# 2_Microcontroler_48.net
KiCad netlist of a schematic drawn in Altium Designer
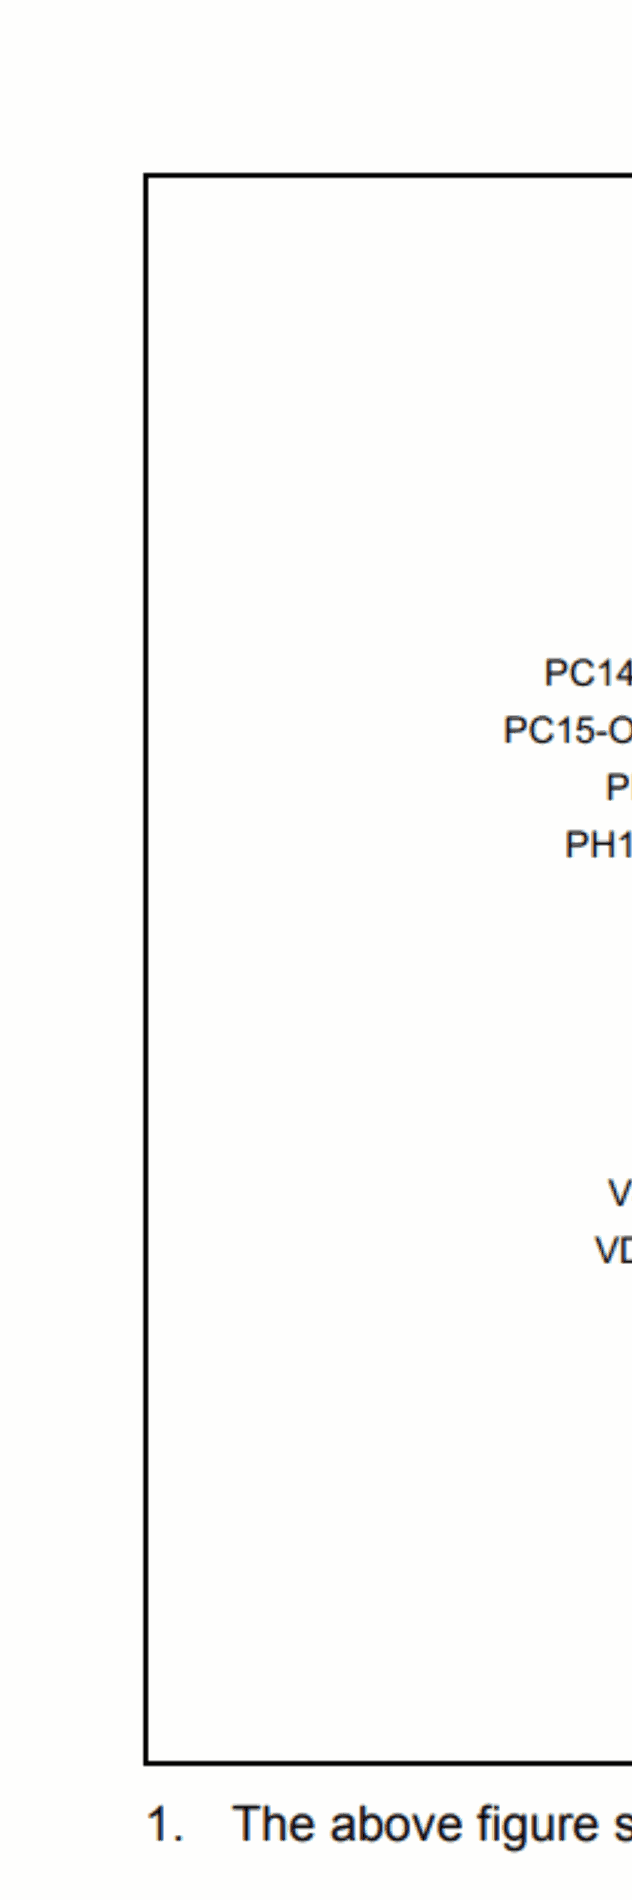
[diagram p0: 2_Microcontroler_48.SchDoc, top left]
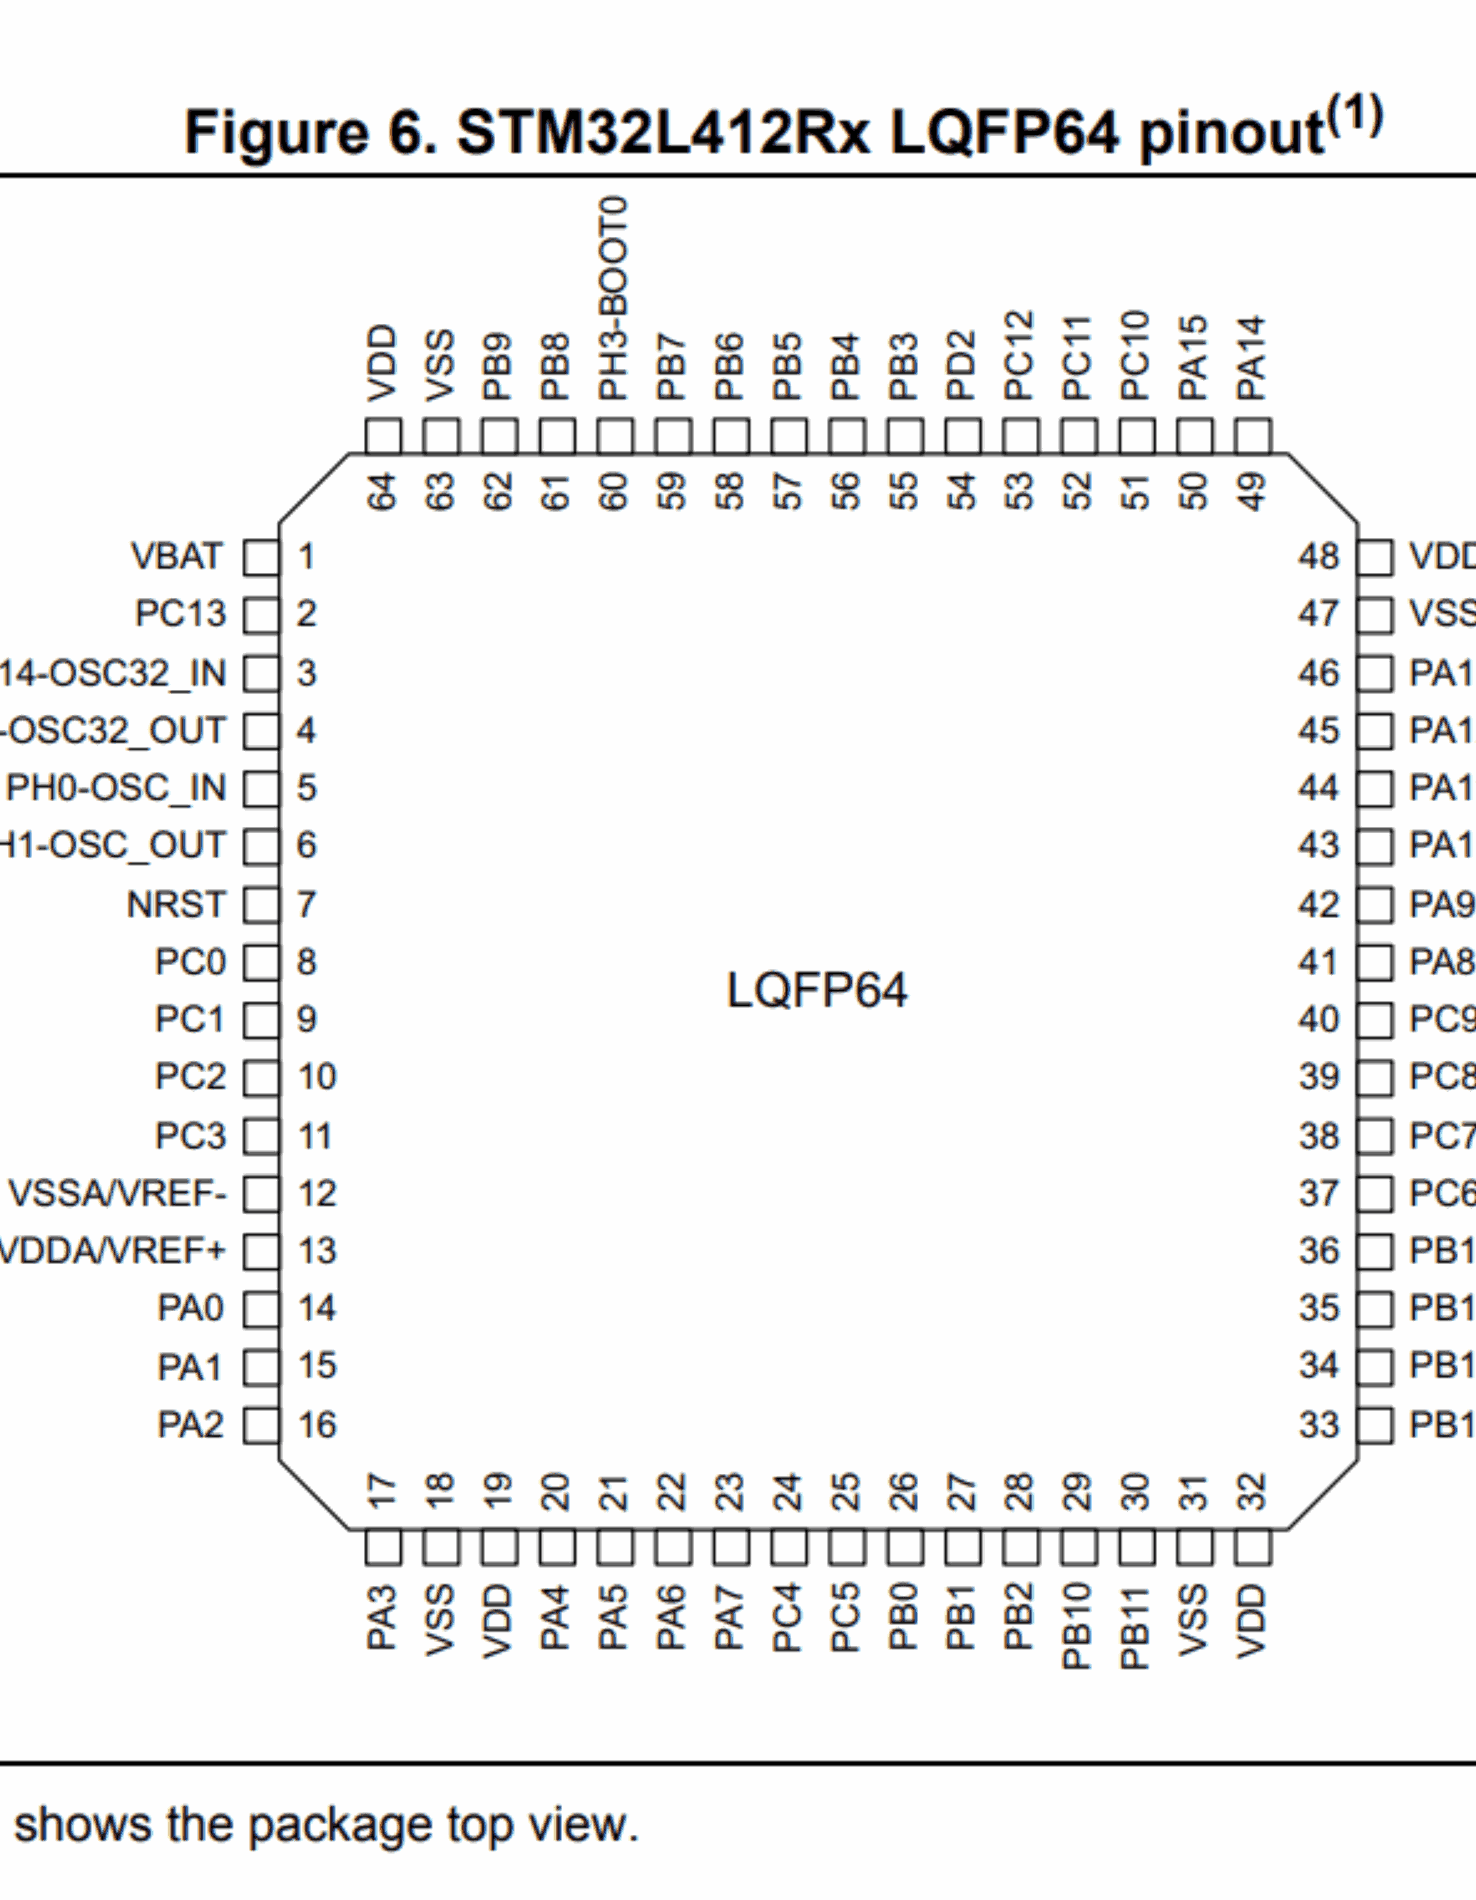
[diagram p1: 2_Microcontroler_48.SchDoc, top middle]
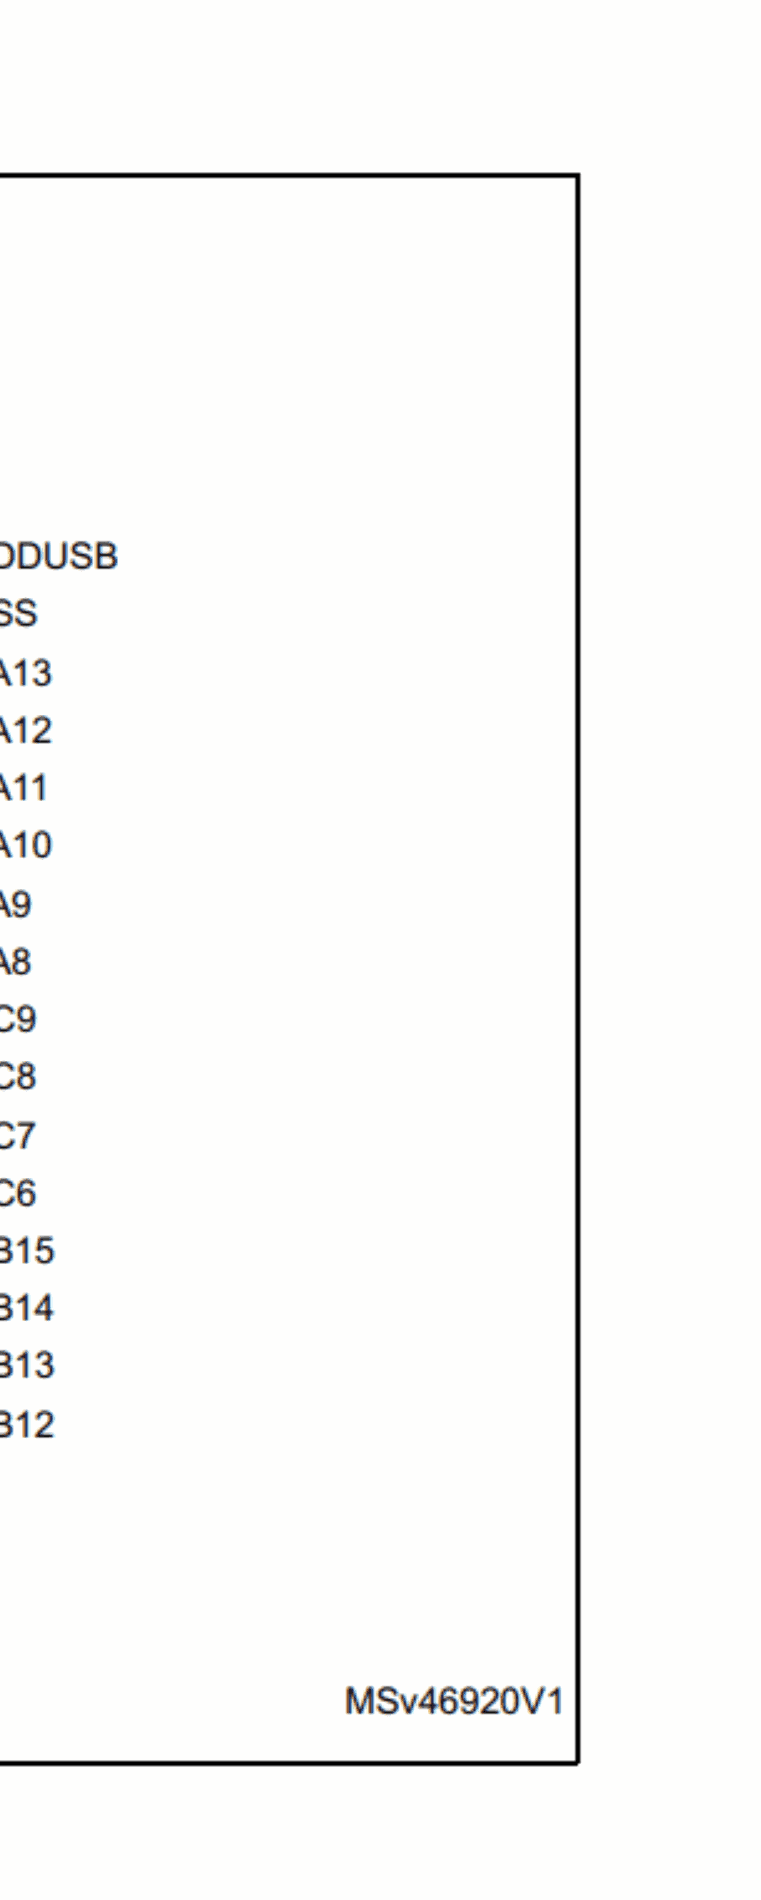
[diagram p2: 2_Microcontroler_48.SchDoc, top right]
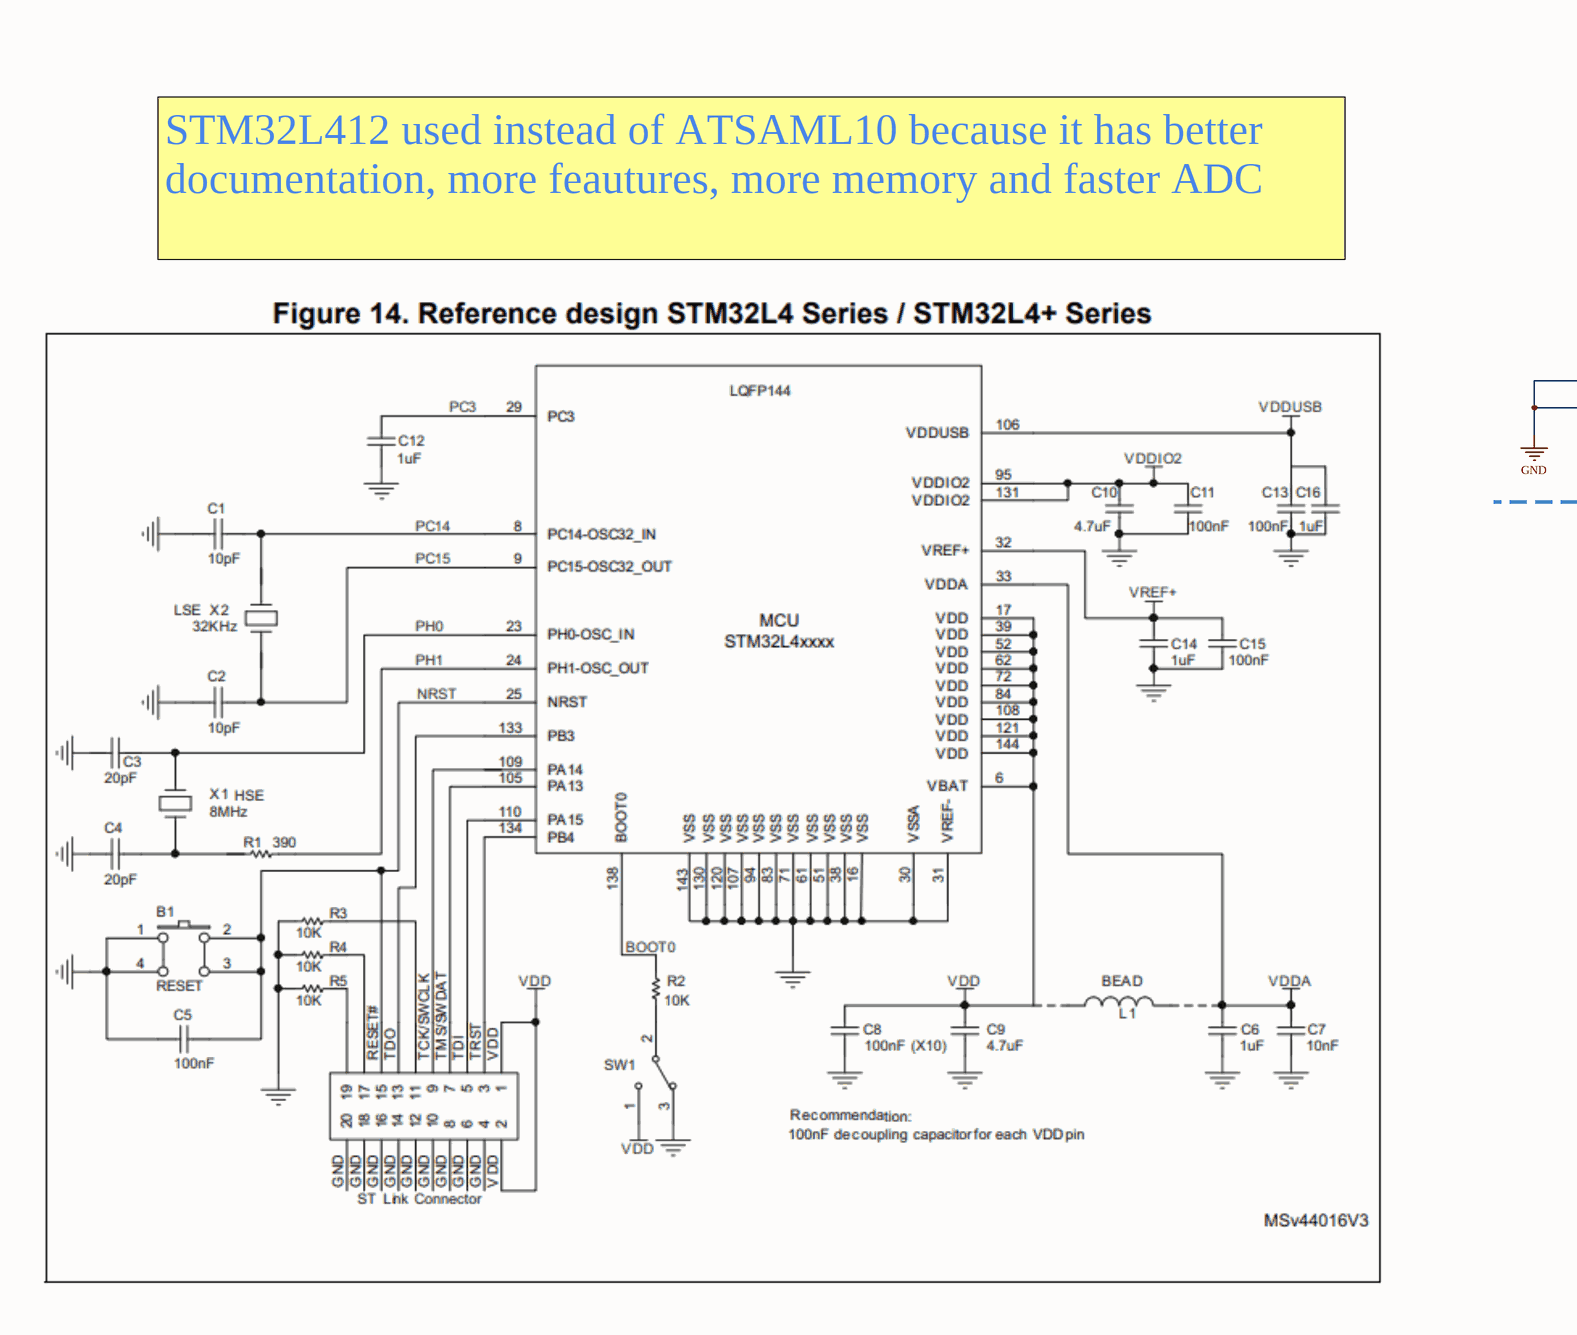
[diagram p3: 2_Microcontroler_48.SchDoc, bottom left]
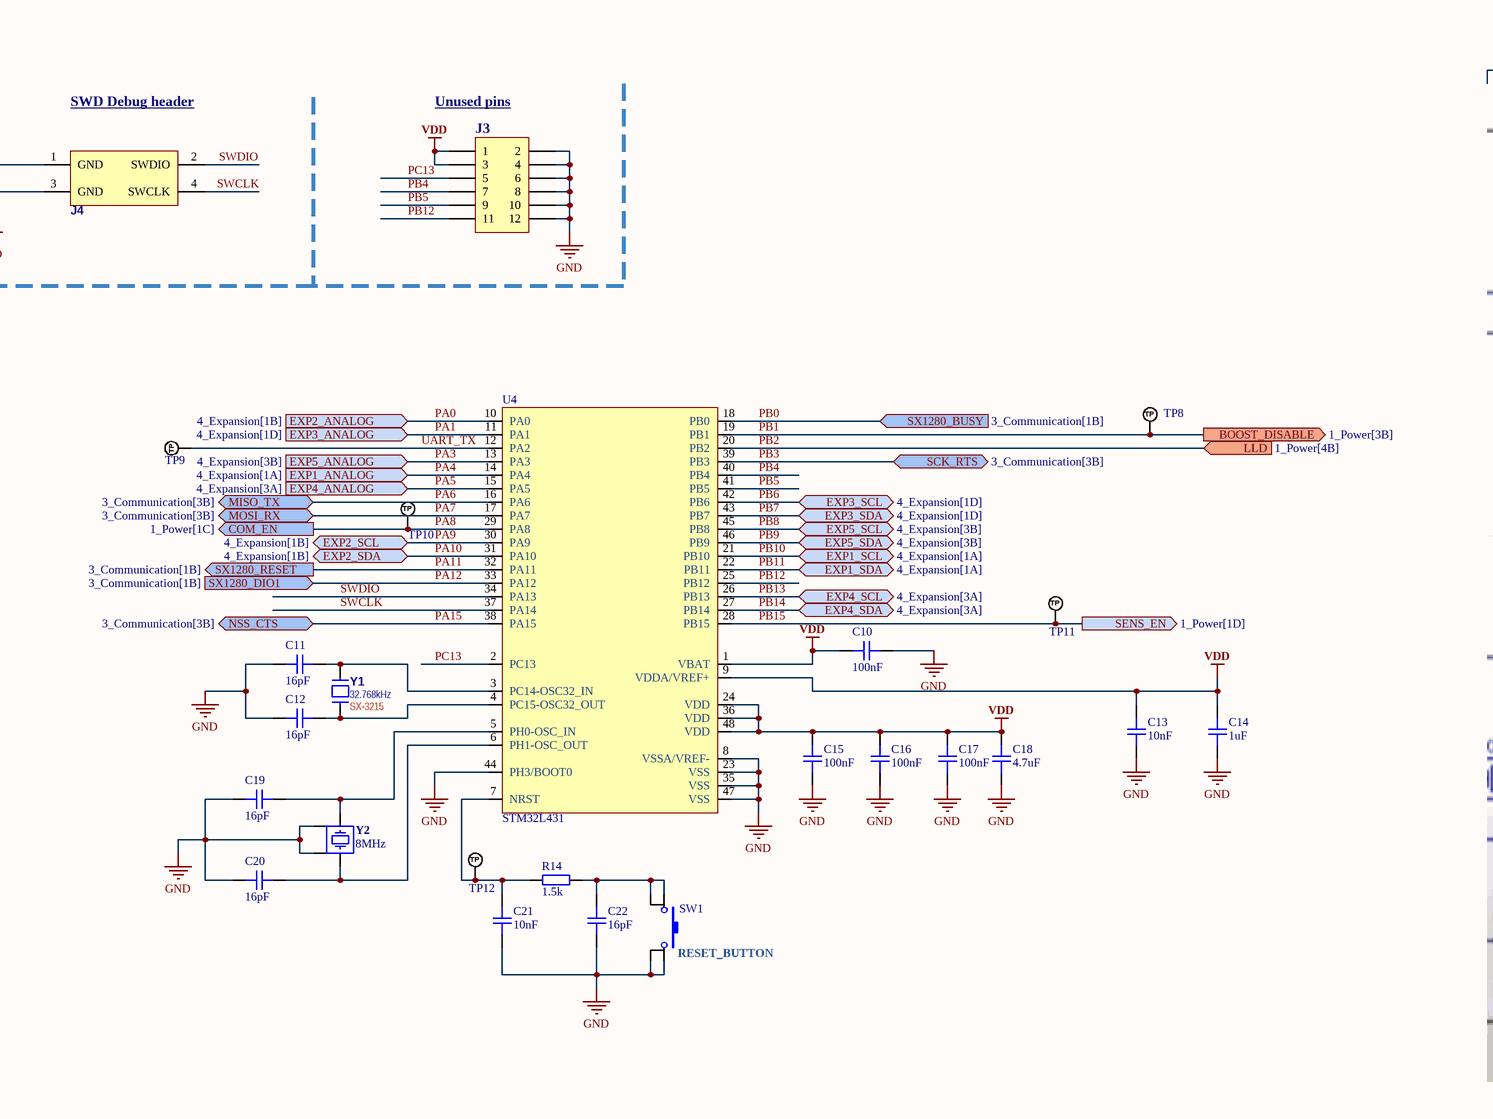
[diagram p4: 2_Microcontroler_48.SchDoc, bottom middle]
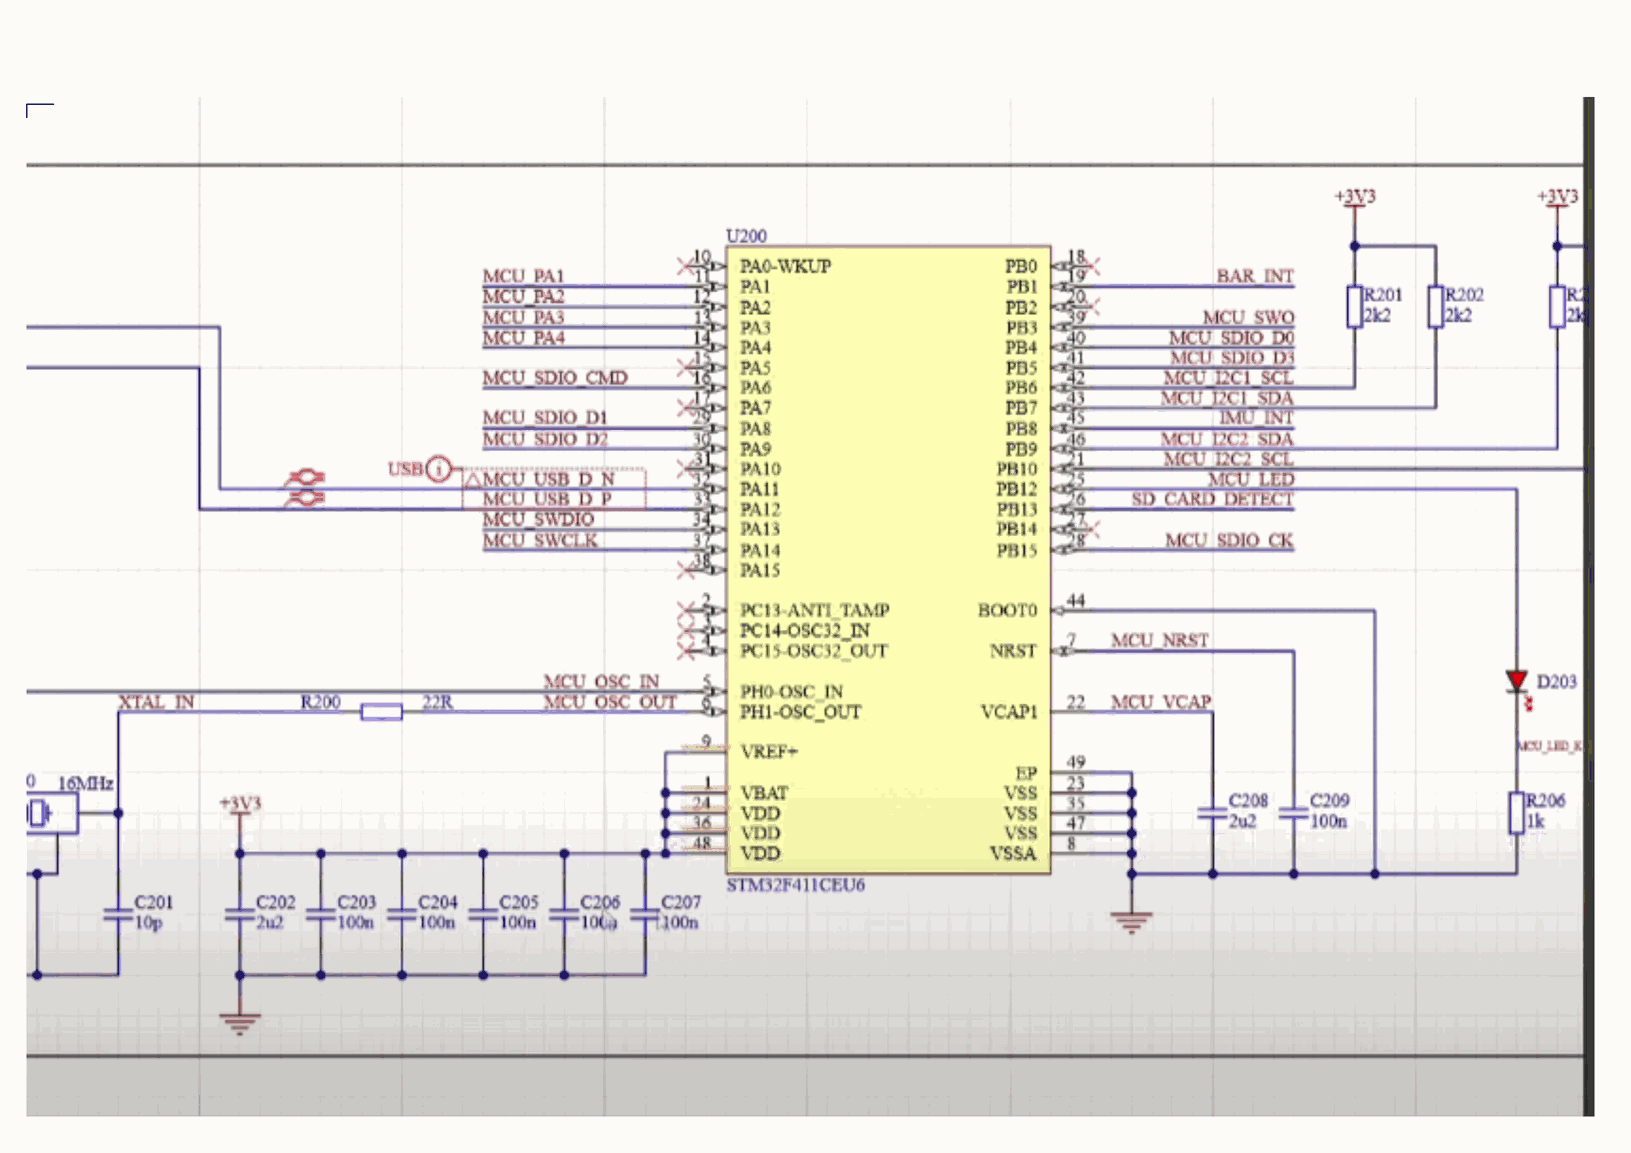
[diagram p5: 2_Microcontroler_48.SchDoc, bottom right]

(export (version "E")
  (design (tool "Eeschema 10.0.6"))
  (components
    (comp (ref "C10")
      (value "100nF")
      (footprint "C0603")
      (description "Capacitor SMD 0603")
      (libsource (lib "Schlib_H2") (part "CAP_0603"))
    )
    (comp (ref "C11")
      (value "16pF")
      (footprint "C0603")
      (description "Capacitor SMD 0603")
      (libsource (lib "Schlib_H2") (part "CAP_0603"))
    )
    (comp (ref "C12")
      (value "16pF")
      (footprint "C0603")
      (description "Capacitor SMD 0603")
      (libsource (lib "Schlib_H2") (part "CAP_0603"))
    )
    (comp (ref "C13")
      (value "10nF")
      (footprint "C0603")
      (description "Capacitor SMD 0603")
      (libsource (lib "Schlib_H2") (part "CAP_0603"))
    )
    (comp (ref "C14")
      (value "1uF")
      (footprint "C0603")
      (description "Capacitor SMD 0603")
      (libsource (lib "Schlib_H2") (part "CAP_0603"))
    )
    (comp (ref "C15")
      (value "100nF")
      (footprint "C0603")
      (description "Capacitor SMD 0603")
      (libsource (lib "Schlib_H2") (part "CAP_0603"))
    )
    (comp (ref "C16")
      (value "100nF")
      (footprint "C0603")
      (description "Capacitor SMD 0603")
      (libsource (lib "Schlib_H2") (part "CAP_0603"))
    )
    (comp (ref "C17")
      (value "100nF")
      (footprint "C0603")
      (description "Capacitor SMD 0603")
      (libsource (lib "Schlib_H2") (part "CAP_0603"))
    )
    (comp (ref "C18")
      (value "4.7uF")
      (footprint "C0603")
      (description "Capacitor SMD 0603")
      (libsource (lib "Schlib_H2") (part "CAP_0603"))
    )
    (comp (ref "C19")
      (value "16pF")
      (footprint "C0603")
      (description "Capacitor SMD 0603")
      (libsource (lib "Schlib_H2") (part "CAP_0603"))
    )
    (comp (ref "C20")
      (value "16pF")
      (footprint "C0603")
      (description "Capacitor SMD 0603")
      (libsource (lib "Schlib_H2") (part "CAP_0603"))
    )
    (comp (ref "C21")
      (value "10nF")
      (footprint "C0603")
      (description "Capacitor SMD 0603")
      (libsource (lib "Schlib_H2") (part "CAP_0603"))
    )
    (comp (ref "C22")
      (value "16pF")
      (footprint "C0603")
      (description "Capacitor SMD 0603")
      (libsource (lib "Schlib_H2") (part "CAP_0603"))
    )
    (comp (ref "J3")
      (value "Header 6X2")
      (footprint "HEADER_6x2_2.54")
      (description "Header, 12-Pin, Dual row")
      (fields (field (name "PUBLISHER") "Altium Limited"))
      (libsource (lib "Schlib_H2") (part "Header 6x2"))
    )
    (comp (ref "J4")
      (value "SWD connector")
      (footprint "HEADER_2x2_2.54")
      (description "Single Wire Debug connector with UART _TX pin")
      (libsource (lib "Schlib_H2") (part "SWD connector"))
    )
    (comp (ref "R14")
      (value "1.5k")
      (footprint "R0603")
      (description "Resistor SMD 0603")
      (libsource (lib "Schlib_H2") (part "RES_0603"))
    )
    (comp (ref "SW1")
      (value "PTS645SM43SMTR92 LFS")
      (footprint "SW_SKRPACE010")
      (description "Switch")
      (fields (field (name "PUBLISHER") "Altium Limited"))
      (libsource (lib "Schlib_H2") (part "SW-PB"))
    )
    (comp (ref "TP8")
      (value "TP_NOBOM")
      (footprint "TEST_PAD_THD")
      (description "Test Point Round 1mm (NO BOM)")
      (libsource (lib "Schlib_H2") (part "TEST_POINT_RND_1MM"))
    )
    (comp (ref "TP9")
      (value "TP_NOBOM")
      (footprint "TEST_PAD_THD")
      (description "Test Point Round 1mm (NO BOM)")
      (libsource (lib "Schlib_H2") (part "TEST_POINT_RND_1MM"))
    )
    (comp (ref "TP10")
      (value "TP_NOBOM")
      (footprint "TEST_PAD_THD")
      (description "Test Point Round 1mm (NO BOM)")
      (libsource (lib "Schlib_H2") (part "TEST_POINT_RND_1MM"))
    )
    (comp (ref "TP11")
      (value "TP_NOBOM")
      (footprint "TEST_PAD_THD")
      (description "Test Point Round 1mm (NO BOM)")
      (libsource (lib "Schlib_H2") (part "TEST_POINT_RND_1MM"))
    )
    (comp (ref "TP12")
      (value "TP_NOBOM")
      (footprint "TEST_PAD_THD")
      (description "Test Point Round 1mm (NO BOM)")
      (libsource (lib "Schlib_H2") (part "TEST_POINT_RND_1MM"))
    )
    (comp (ref "U4")
      (value "STM32L431")
      (footprint "QFPN-48")
      (description "Ultra-low-power Arm® Cortex®-M4 32-bit MCU+FPU, 100DMIPS,\r\n up to 128KB flash, 40KB SRAM(LQFP48)")
      (libsource (lib "Schlib_H2") (part "STM32L431"))
    )
    (comp (ref "Y1")
      (value "32.768kHz")
      (footprint "CRYSTAL_SX-3215")
      (description "Crystal")
      (fields (field (name "PACKAGEREFERENCE") "SX-3215"))
      (libsource (lib "Schlib_H2") (part "CRYSTAL_1"))
    )
    (comp (ref "Y2")
      (value "8MHz")
      (footprint "CRYSTAL_ECX-32_3.2x2.5x0.8 - duplicate")
      (description "Crystal")
      (fields
        (field (name "MANUFACTURER") "Epson")
        (field (name "MANUFACTURER PART NUMBER") "TSX-3225 24.0000MF15X-AC")
      )
      (libsource (lib "Schlib_H2") (part "Crystal"))
    )
  )
  (nets
    (net (code "1") (name "/PA0") (class "Default")
      (node (ref "U4") (pin "10") (pinfunction "PA0_10") (pintype "passive"))
    )
    (net (code "2") (name "/PA1") (class "Default")
      (node (ref "U4") (pin "11") (pinfunction "PA1_11") (pintype "passive"))
    )
    (net (code "3") (name "/PA3") (class "Default")
      (node (ref "U4") (pin "13") (pinfunction "PA3_13") (pintype "passive"))
    )
    (net (code "4") (name "/PA4") (class "Default")
      (node (ref "U4") (pin "14") (pinfunction "PA4_14") (pintype "passive"))
    )
    (net (code "5") (name "/PA5") (class "Default")
      (node (ref "U4") (pin "15") (pinfunction "PA5_15") (pintype "passive"))
    )
    (net (code "6") (name "/PA6") (class "Default")
      (node (ref "U4") (pin "16") (pinfunction "PA6_16") (pintype "passive"))
    )
    (net (code "7") (name "/PA7") (class "Default")
      (node (ref "U4") (pin "17") (pinfunction "PA7_17") (pintype "passive"))
    )
    (net (code "8") (name "/PA8") (class "Default")
      (node (ref "TP10") (pin "1") (pinfunction "TP_1") (pintype "passive"))
      (node (ref "U4") (pin "29") (pinfunction "PA8_29") (pintype "passive"))
    )
    (net (code "9") (name "/PA9") (class "Default")
      (node (ref "U4") (pin "30") (pinfunction "PA9_30") (pintype "passive"))
    )
    (net (code "10") (name "/PA10") (class "Default")
      (node (ref "U4") (pin "31") (pinfunction "PA10_31") (pintype "passive"))
    )
    (net (code "11") (name "/PA11") (class "Default")
      (node (ref "U4") (pin "32") (pinfunction "PA11_32") (pintype "passive"))
    )
    (net (code "12") (name "/PA12") (class "Default")
      (node (ref "U4") (pin "33") (pinfunction "PA12_33") (pintype "passive"))
    )
    (net (code "13") (name "/PA15") (class "Default")
      (node (ref "U4") (pin "38") (pinfunction "PA15_38") (pintype "passive"))
    )
    (net (code "14") (name "/PB0") (class "Default")
      (node (ref "U4") (pin "18") (pinfunction "PB0_18") (pintype "passive"))
    )
    (net (code "15") (name "/PB1") (class "Default")
      (node (ref "TP8") (pin "1") (pinfunction "TP_1") (pintype "passive"))
      (node (ref "U4") (pin "19") (pinfunction "PB1_19") (pintype "passive"))
    )
    (net (code "16") (name "/PB2") (class "Default")
      (node (ref "U4") (pin "20") (pinfunction "PB2_20") (pintype "passive"))
    )
    (net (code "17") (name "/PB3") (class "Default")
      (node (ref "U4") (pin "39") (pinfunction "PB3_39") (pintype "passive"))
    )
    (net (code "18") (name "/PB4") (class "Default")
      (node (ref "J3") (pin "7") (pinfunction "7_7") (pintype "passive"))
      (node (ref "U4") (pin "40") (pinfunction "PB4_40") (pintype "passive"))
    )
    (net (code "19") (name "/PB5") (class "Default")
      (node (ref "J3") (pin "9") (pinfunction "9_9") (pintype "passive"))
      (node (ref "U4") (pin "41") (pinfunction "PB5_41") (pintype "passive"))
    )
    (net (code "20") (name "/PB6") (class "Default")
      (node (ref "U4") (pin "42") (pinfunction "PB6_42") (pintype "passive"))
    )
    (net (code "21") (name "/PB7") (class "Default")
      (node (ref "U4") (pin "43") (pinfunction "PB7_43") (pintype "passive"))
    )
    (net (code "22") (name "/PB8") (class "Default")
      (node (ref "U4") (pin "45") (pinfunction "PB8_45") (pintype "passive"))
    )
    (net (code "23") (name "/PB9") (class "Default")
      (node (ref "U4") (pin "46") (pinfunction "PB9_46") (pintype "passive"))
    )
    (net (code "24") (name "/PB10") (class "Default")
      (node (ref "U4") (pin "21") (pinfunction "PB10_21") (pintype "passive"))
    )
    (net (code "25") (name "/PB11") (class "Default")
      (node (ref "U4") (pin "22") (pinfunction "PB11_22") (pintype "passive"))
    )
    (net (code "26") (name "/PB12") (class "Default")
      (node (ref "J3") (pin "11") (pinfunction "11_11") (pintype "passive"))
      (node (ref "U4") (pin "25") (pinfunction "PB12_25") (pintype "passive"))
    )
    (net (code "27") (name "/PB13") (class "Default")
      (node (ref "U4") (pin "26") (pinfunction "PB13_26") (pintype "passive"))
    )
    (net (code "28") (name "/PB14") (class "Default")
      (node (ref "U4") (pin "27") (pinfunction "PB14_27") (pintype "passive"))
    )
    (net (code "29") (name "/PB15") (class "Default")
      (node (ref "TP11") (pin "1") (pinfunction "TP_1") (pintype "passive"))
      (node (ref "U4") (pin "28") (pinfunction "PB15_28") (pintype "passive"))
    )
    (net (code "30") (name "/PC13") (class "Default")
      (node (ref "J3") (pin "5") (pinfunction "5_5") (pintype "passive"))
      (node (ref "U4") (pin "2") (pinfunction "PC13_2") (pintype "passive"))
    )
    (net (code "31") (name "/SWCLK") (class "Default")
      (node (ref "J4") (pin "4") (pinfunction "SWCLK_4") (pintype "passive"))
      (node (ref "U4") (pin "37") (pinfunction "PA14_37") (pintype "passive"))
    )
    (net (code "32") (name "/SWDIO") (class "Default")
      (node (ref "J4") (pin "2") (pinfunction "SWDIO_2") (pintype "passive"))
      (node (ref "U4") (pin "34") (pinfunction "PA13_34") (pintype "passive"))
    )
    (net (code "33") (name "/UART_TX") (class "Default")
      (node (ref "TP9") (pin "1") (pinfunction "TP_1") (pintype "passive"))
      (node (ref "U4") (pin "12") (pinfunction "PA2_12") (pintype "passive"))
    )
    (net (code "34") (name "GND") (class "Default")
      (node (ref "C10") (pin "1") (pinfunction "1_1") (pintype "passive"))
      (node (ref "C11") (pin "1") (pinfunction "1_1") (pintype "passive"))
      (node (ref "C12") (pin "1") (pinfunction "1_1") (pintype "passive"))
      (node (ref "C13") (pin "1") (pinfunction "1_1") (pintype "passive"))
      (node (ref "C14") (pin "1") (pinfunction "1_1") (pintype "passive"))
      (node (ref "C15") (pin "1") (pinfunction "1_1") (pintype "passive"))
      (node (ref "C16") (pin "1") (pinfunction "1_1") (pintype "passive"))
      (node (ref "C17") (pin "1") (pinfunction "1_1") (pintype "passive"))
      (node (ref "C18") (pin "1") (pinfunction "1_1") (pintype "passive"))
      (node (ref "C19") (pin "1") (pinfunction "1_1") (pintype "passive"))
      (node (ref "C20") (pin "1") (pinfunction "1_1") (pintype "passive"))
      (node (ref "C21") (pin "1") (pinfunction "1_1") (pintype "passive"))
      (node (ref "C22") (pin "1") (pinfunction "1_1") (pintype "passive"))
      (node (ref "J3") (pin "10") (pinfunction "10_10") (pintype "passive"))
      (node (ref "J3") (pin "12") (pinfunction "12_12") (pintype "passive"))
      (node (ref "J3") (pin "2") (pinfunction "2_2") (pintype "passive"))
      (node (ref "J3") (pin "4") (pinfunction "4_4") (pintype "passive"))
      (node (ref "J3") (pin "6") (pinfunction "6_6") (pintype "passive"))
      (node (ref "J3") (pin "8") (pinfunction "8_8") (pintype "passive"))
      (node (ref "J4") (pin "1") (pinfunction "GND_1") (pintype "passive"))
      (node (ref "J4") (pin "3") (pinfunction "GND_3") (pintype "passive"))
      (node (ref "SW1") (pin "3") (pinfunction "3_3") (pintype "passive"))
      (node (ref "SW1") (pin "4") (pinfunction "4_4") (pintype "passive"))
      (node (ref "U4") (pin "23") (pinfunction "VSS_23") (pintype "passive"))
      (node (ref "U4") (pin "35") (pinfunction "VSS_35") (pintype "passive"))
      (node (ref "U4") (pin "44") (pinfunction "PH3/BOOT0_44") (pintype "passive"))
      (node (ref "U4") (pin "47") (pinfunction "VSS_47") (pintype "passive"))
      (node (ref "U4") (pin "8") (pinfunction "VSSA/VREF-_8") (pintype "passive"))
      (node (ref "Y2") (pin "2") (pinfunction "2_2") (pintype "passive"))
      (node (ref "Y2") (pin "4") (pinfunction "4_4") (pintype "passive"))
    )
    (net (code "35") (name "Net-(C22-Pad2)") (class "Default")
      (node (ref "C22") (pin "2") (pinfunction "2_2") (pintype "passive"))
      (node (ref "R14") (pin "2") (pinfunction "2_2") (pintype "passive"))
      (node (ref "SW1") (pin "1") (pinfunction "1_1") (pintype "passive"))
      (node (ref "SW1") (pin "2") (pinfunction "2_2") (pintype "passive"))
    )
    (net (code "36") (name "Net-(TP12-TP)") (class "Default")
      (node (ref "C21") (pin "2") (pinfunction "2_2") (pintype "passive"))
      (node (ref "R14") (pin "1") (pinfunction "1_1") (pintype "passive"))
      (node (ref "TP12") (pin "1") (pinfunction "TP_1") (pintype "passive"))
      (node (ref "U4") (pin "7") (pinfunction "NRST_7") (pintype "passive"))
    )
    (net (code "37") (name "Net-(U4-PC14-OSC32_IN)") (class "Default")
      (node (ref "C11") (pin "2") (pinfunction "2_2") (pintype "passive"))
      (node (ref "U4") (pin "3") (pinfunction "PC14-OSC32_IN_3") (pintype "passive"))
      (node (ref "Y1") (pin "2") (pinfunction "2_2") (pintype "passive"))
    )
    (net (code "38") (name "Net-(U4-PC15-OSC32_OUT)") (class "Default")
      (node (ref "C12") (pin "2") (pinfunction "2_2") (pintype "passive"))
      (node (ref "U4") (pin "4") (pinfunction "PC15-OSC32_OUT_4") (pintype "passive"))
      (node (ref "Y1") (pin "1") (pinfunction "1_1") (pintype "passive"))
    )
    (net (code "39") (name "Net-(U4-PH0-OSC_IN)") (class "Default")
      (node (ref "C19") (pin "2") (pinfunction "2_2") (pintype "passive"))
      (node (ref "U4") (pin "5") (pinfunction "PH0-OSC_IN_5") (pintype "passive"))
      (node (ref "Y2") (pin "3") (pinfunction "3_3") (pintype "passive"))
    )
    (net (code "40") (name "Net-(U4-PH1-OSC_OUT)") (class "Default")
      (node (ref "C20") (pin "2") (pinfunction "2_2") (pintype "passive"))
      (node (ref "U4") (pin "6") (pinfunction "PH1-OSC_OUT_6") (pintype "passive"))
      (node (ref "Y2") (pin "1") (pinfunction "1_1") (pintype "passive"))
    )
    (net (code "41") (name "VDD") (class "Default")
      (node (ref "C10") (pin "2") (pinfunction "2_2") (pintype "passive"))
      (node (ref "C13") (pin "2") (pinfunction "2_2") (pintype "passive"))
      (node (ref "C14") (pin "2") (pinfunction "2_2") (pintype "passive"))
      (node (ref "C15") (pin "2") (pinfunction "2_2") (pintype "passive"))
      (node (ref "C16") (pin "2") (pinfunction "2_2") (pintype "passive"))
      (node (ref "C17") (pin "2") (pinfunction "2_2") (pintype "passive"))
      (node (ref "C18") (pin "2") (pinfunction "2_2") (pintype "passive"))
      (node (ref "J3") (pin "1") (pinfunction "1_1") (pintype "passive"))
      (node (ref "J3") (pin "3") (pinfunction "3_3") (pintype "passive"))
      (node (ref "U4") (pin "1") (pinfunction "VBAT_1") (pintype "passive"))
      (node (ref "U4") (pin "24") (pinfunction "VDD_24") (pintype "passive"))
      (node (ref "U4") (pin "36") (pinfunction "VDD_36") (pintype "passive"))
      (node (ref "U4") (pin "48") (pinfunction "VDD_48") (pintype "passive"))
      (node (ref "U4") (pin "9") (pinfunction "VDDA/VREF+_9") (pintype "passive"))
    )
  )
)
